# TUDSSL_condenar__Hardware_PCBs_Logger_Sc.net
KiCad netlist of a schematic drawn in Altium Designer
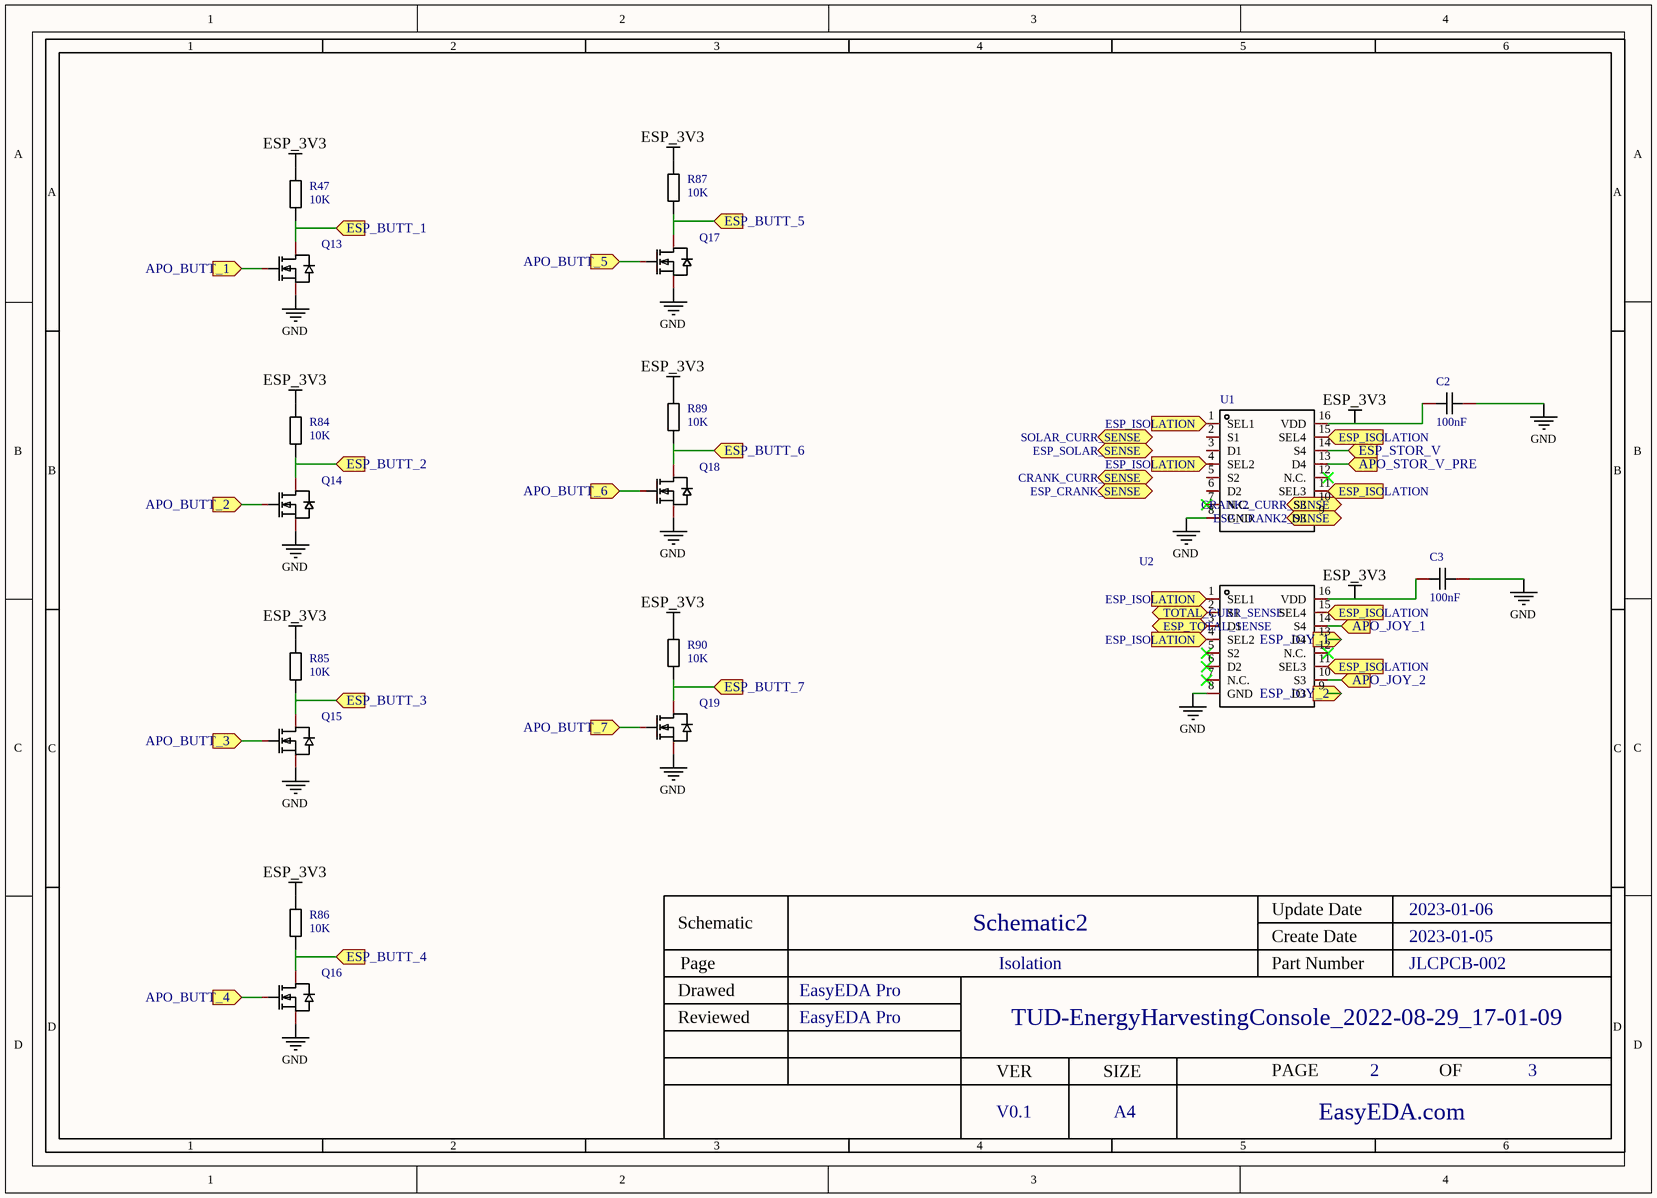
[diagram p0: TUDSSL_condenar__Hardware_PCBs_Logger_Schematic2__2_Isolation.schdoc]

(export (version "E")
  (design (tool "Eeschema 10.0.6"))
  (components
    (comp (ref "C2")
      (value "100nF")
      (fields
        (field (name "NAME") "100nF")
        (field (name "MANUFACTURER") "YAGEO")
        (field (name "MANUFACTURER PART") "CC0603KRX7R9BB104")
      )
      (libsource (lib "altium-import") (part "root_2_CC0603KRX7R9BB104_"))
    )
    (comp (ref "C3")
      (value "100nF")
      (fields
        (field (name "NAME") "100nF")
        (field (name "MANUFACTURER") "YAGEO")
        (field (name "MANUFACTURER PART") "CC0603KRX7R9BB104")
      )
      (libsource (lib "altium-import") (part "root_0_CC0603KRX7R9BB104_"))
    )
    (comp (ref "Q13")
      (value "SI2302")
      (fields (field (name "MANUFACTURER") "YONGYUTAI(永裕泰)"))
      (libsource (lib "altium-import") (part "root_0_SI2302_"))
    )
    (comp (ref "Q14")
      (value "SI2302")
      (fields (field (name "MANUFACTURER") "YONGYUTAI(永裕泰)"))
      (libsource (lib "altium-import") (part "root_0_SI2302_"))
    )
    (comp (ref "Q15")
      (value "SI2302")
      (fields (field (name "MANUFACTURER") "YONGYUTAI(永裕泰)"))
      (libsource (lib "altium-import") (part "root_0_SI2302_"))
    )
    (comp (ref "Q16")
      (value "SI2302")
      (fields (field (name "MANUFACTURER") "YONGYUTAI(永裕泰)"))
      (libsource (lib "altium-import") (part "root_0_SI2302_"))
    )
    (comp (ref "Q17")
      (value "SI2302")
      (fields (field (name "MANUFACTURER") "YONGYUTAI(永裕泰)"))
      (libsource (lib "altium-import") (part "root_0_SI2302_"))
    )
    (comp (ref "Q18")
      (value "SI2302")
      (fields (field (name "MANUFACTURER") "YONGYUTAI(永裕泰)"))
      (libsource (lib "altium-import") (part "root_0_SI2302_"))
    )
    (comp (ref "Q19")
      (value "SI2302")
      (fields (field (name "MANUFACTURER") "YONGYUTAI(永裕泰)"))
      (libsource (lib "altium-import") (part "root_0_SI2302_"))
    )
    (comp (ref "R47")
      (value "10K")
      (fields
        (field (name "NAME") "10K")
        (field (name "MANUFACTURER") "UniOhm")
        (field (name "MANUFACTURER PART") "0603WAF1002T5E")
      )
      (libsource (lib "altium-import") (part "root_3_0603WAF1002T5E_"))
    )
    (comp (ref "R84")
      (value "10K")
      (fields
        (field (name "NAME") "10K")
        (field (name "MANUFACTURER") "UniOhm")
        (field (name "MANUFACTURER PART") "0603WAF1002T5E")
      )
      (libsource (lib "altium-import") (part "root_3_0603WAF1002T5E_"))
    )
    (comp (ref "R85")
      (value "10K")
      (fields
        (field (name "NAME") "10K")
        (field (name "MANUFACTURER") "UniOhm")
        (field (name "MANUFACTURER PART") "0603WAF1002T5E")
      )
      (libsource (lib "altium-import") (part "root_3_0603WAF1002T5E_"))
    )
    (comp (ref "R86")
      (value "10K")
      (fields
        (field (name "NAME") "10K")
        (field (name "MANUFACTURER") "UniOhm")
        (field (name "MANUFACTURER PART") "0603WAF1002T5E")
      )
      (libsource (lib "altium-import") (part "root_3_0603WAF1002T5E_"))
    )
    (comp (ref "R87")
      (value "10K")
      (fields
        (field (name "NAME") "10K")
        (field (name "MANUFACTURER") "UniOhm")
        (field (name "MANUFACTURER PART") "0603WAF1002T5E")
      )
      (libsource (lib "altium-import") (part "root_3_0603WAF1002T5E_"))
    )
    (comp (ref "R89")
      (value "10K")
      (fields
        (field (name "NAME") "10K")
        (field (name "MANUFACTURER") "UniOhm")
        (field (name "MANUFACTURER PART") "0603WAF1002T5E")
      )
      (libsource (lib "altium-import") (part "root_3_0603WAF1002T5E_"))
    )
    (comp (ref "R90")
      (value "10K")
      (fields
        (field (name "NAME") "10K")
        (field (name "MANUFACTURER") "UniOhm")
        (field (name "MANUFACTURER PART") "0603WAF1002T5E")
      )
      (libsource (lib "altium-import") (part "root_3_0603WAF1002T5E_"))
    )
    (comp (ref "U1")
      (value "TMUX1511RSVR")
      (description "Switch Circuit:-")
      (fields (field (name "MANUFACTURER") "TI(德州仪器)"))
      (libsource (lib "altium-import") (part "root_0_TMUX1511RSVR_"))
    )
    (comp (ref "U2")
      (value "TMUX1511RSVR")
      (description "Switch Circuit:-")
      (fields (field (name "MANUFACTURER") "TI(德州仪器)"))
      (libsource (lib "altium-import") (part "root_0_TMUX1511RSVR_"))
    )
  )
  (nets
    (net (code "1") (name "/APO_BUTT_1") (class "Default")
      (node (ref "Q13") (pin "1") (pinfunction "G_1") (pintype "passive"))
    )
    (net (code "2") (name "/APO_BUTT_2") (class "Default")
      (node (ref "Q14") (pin "1") (pinfunction "G_1") (pintype "passive"))
    )
    (net (code "3") (name "/APO_BUTT_3") (class "Default")
      (node (ref "Q15") (pin "1") (pinfunction "G_1") (pintype "passive"))
    )
    (net (code "4") (name "/APO_BUTT_4") (class "Default")
      (node (ref "Q16") (pin "1") (pinfunction "G_1") (pintype "passive"))
    )
    (net (code "5") (name "/APO_BUTT_5") (class "Default")
      (node (ref "Q17") (pin "1") (pinfunction "G_1") (pintype "passive"))
    )
    (net (code "6") (name "/APO_BUTT_6") (class "Default")
      (node (ref "Q18") (pin "1") (pinfunction "G_1") (pintype "passive"))
    )
    (net (code "7") (name "/APO_BUTT_7") (class "Default")
      (node (ref "Q19") (pin "1") (pinfunction "G_1") (pintype "passive"))
    )
    (net (code "8") (name "/APO_JOY_1") (class "Default")
      (node (ref "U2") (pin "14") (pinfunction "S4_14") (pintype "passive"))
    )
    (net (code "9") (name "/APO_JOY_2") (class "Default")
      (node (ref "U2") (pin "10") (pinfunction "S3_10") (pintype "passive"))
    )
    (net (code "10") (name "/APO_STOR_V_PRE") (class "Default")
      (node (ref "U1") (pin "13") (pinfunction "D4_13") (pintype "passive"))
    )
    (net (code "13") (name "/ESP_BUTT_1") (class "Default")
      (node (ref "Q13") (pin "3") (pinfunction "D_3") (pintype "passive"))
      (node (ref "R47") (pin "2") (pinfunction "2_2") (pintype "passive"))
    )
    (net (code "14") (name "/ESP_BUTT_2") (class "Default")
      (node (ref "Q14") (pin "3") (pinfunction "D_3") (pintype "passive"))
      (node (ref "R84") (pin "2") (pinfunction "2_2") (pintype "passive"))
    )
    (net (code "15") (name "/ESP_BUTT_3") (class "Default")
      (node (ref "Q15") (pin "3") (pinfunction "D_3") (pintype "passive"))
      (node (ref "R85") (pin "2") (pinfunction "2_2") (pintype "passive"))
    )
    (net (code "16") (name "/ESP_BUTT_4") (class "Default")
      (node (ref "Q16") (pin "3") (pinfunction "D_3") (pintype "passive"))
      (node (ref "R86") (pin "2") (pinfunction "2_2") (pintype "passive"))
    )
    (net (code "17") (name "/ESP_BUTT_5") (class "Default")
      (node (ref "Q17") (pin "3") (pinfunction "D_3") (pintype "passive"))
      (node (ref "R87") (pin "2") (pinfunction "2_2") (pintype "passive"))
    )
    (net (code "18") (name "/ESP_BUTT_6") (class "Default")
      (node (ref "Q18") (pin "3") (pinfunction "D_3") (pintype "passive"))
      (node (ref "R89") (pin "2") (pinfunction "2_2") (pintype "passive"))
    )
    (net (code "19") (name "/ESP_BUTT_7") (class "Default")
      (node (ref "Q19") (pin "3") (pinfunction "D_3") (pintype "passive"))
      (node (ref "R90") (pin "2") (pinfunction "2_2") (pintype "passive"))
    )
    (net (code "22") (name "/ESP_ISOLATION") (class "Default")
      (node (ref "U1") (pin "1") (pinfunction "SEL1_1") (pintype "passive"))
      (node (ref "U1") (pin "11") (pinfunction "SEL3_11") (pintype "passive"))
      (node (ref "U1") (pin "15") (pinfunction "SEL4_15") (pintype "passive"))
      (node (ref "U1") (pin "4") (pinfunction "SEL2_4") (pintype "passive"))
      (node (ref "U2") (pin "1") (pinfunction "SEL1_1") (pintype "passive"))
      (node (ref "U2") (pin "11") (pinfunction "SEL3_11") (pintype "passive"))
      (node (ref "U2") (pin "15") (pinfunction "SEL4_15") (pintype "passive"))
      (node (ref "U2") (pin "4") (pinfunction "SEL2_4") (pintype "passive"))
    )
    (net (code "23") (name "/ESP_JOY_1") (class "Default")
      (node (ref "U2") (pin "13") (pinfunction "D4_13") (pintype "passive"))
    )
    (net (code "24") (name "/ESP_JOY_2") (class "Default")
      (node (ref "U2") (pin "9") (pinfunction "D3_9") (pintype "passive"))
    )
    (net (code "26") (name "/ESP_STOR_V") (class "Default")
      (node (ref "U1") (pin "14") (pinfunction "S4_14") (pintype "passive"))
    )
    (net (code "30") (name "ESP_3V3") (class "Default")
      (node (ref "C2") (pin "2") (pinfunction "2_2") (pintype "passive"))
      (node (ref "C3") (pin "1") (pinfunction "1_1") (pintype "passive"))
      (node (ref "R47") (pin "1") (pinfunction "1_1") (pintype "passive"))
      (node (ref "R84") (pin "1") (pinfunction "1_1") (pintype "passive"))
      (node (ref "R85") (pin "1") (pinfunction "1_1") (pintype "passive"))
      (node (ref "R86") (pin "1") (pinfunction "1_1") (pintype "passive"))
      (node (ref "R87") (pin "1") (pinfunction "1_1") (pintype "passive"))
      (node (ref "R89") (pin "1") (pinfunction "1_1") (pintype "passive"))
      (node (ref "R90") (pin "1") (pinfunction "1_1") (pintype "passive"))
      (node (ref "U1") (pin "16") (pinfunction "VDD_16") (pintype "passive"))
      (node (ref "U2") (pin "16") (pinfunction "VDD_16") (pintype "passive"))
    )
    (net (code "31") (name "GND") (class "Default")
      (node (ref "C2") (pin "1") (pinfunction "1_1") (pintype "passive"))
      (node (ref "C3") (pin "2") (pinfunction "2_2") (pintype "passive"))
      (node (ref "Q13") (pin "2") (pinfunction "S_2") (pintype "passive"))
      (node (ref "Q14") (pin "2") (pinfunction "S_2") (pintype "passive"))
      (node (ref "Q15") (pin "2") (pinfunction "S_2") (pintype "passive"))
      (node (ref "Q16") (pin "2") (pinfunction "S_2") (pintype "passive"))
      (node (ref "Q17") (pin "2") (pinfunction "S_2") (pintype "passive"))
      (node (ref "Q18") (pin "2") (pinfunction "S_2") (pintype "passive"))
      (node (ref "Q19") (pin "2") (pinfunction "S_2") (pintype "passive"))
      (node (ref "U1") (pin "8") (pinfunction "GND_8") (pintype "passive"))
      (node (ref "U2") (pin "8") (pinfunction "GND_8") (pintype "passive"))
    )
    (net (code "32") (name "unconnected-(U1-D1-Pad3)") (class "Default")
      (node (ref "U1") (pin "3") (pinfunction "D1_3") (pintype "passive"))
    )
    (net (code "33") (name "unconnected-(U1-D2-Pad6)") (class "Default")
      (node (ref "U1") (pin "6") (pinfunction "D2_6") (pintype "passive"))
    )
    (net (code "34") (name "unconnected-(U1-D3-Pad9)") (class "Default")
      (node (ref "U1") (pin "9") (pinfunction "D3_9") (pintype "passive"))
    )
    (net (code "35") (name "unconnected-(U1-N.C.-Pad7)") (class "Default")
      (node (ref "U1") (pin "7") (pinfunction "N.C._7") (pintype "passive+no_connect"))
    )
    (net (code "36") (name "unconnected-(U1-N.C.-Pad12)") (class "Default")
      (node (ref "U1") (pin "12") (pinfunction "N.C._12") (pintype "passive+no_connect"))
    )
    (net (code "37") (name "unconnected-(U1-S1-Pad2)") (class "Default")
      (node (ref "U1") (pin "2") (pinfunction "S1_2") (pintype "passive"))
    )
    (net (code "38") (name "unconnected-(U1-S2-Pad5)") (class "Default")
      (node (ref "U1") (pin "5") (pinfunction "S2_5") (pintype "passive"))
    )
    (net (code "39") (name "unconnected-(U1-S3-Pad10)") (class "Default")
      (node (ref "U1") (pin "10") (pinfunction "S3_10") (pintype "passive"))
    )
    (net (code "40") (name "unconnected-(U2-D1-Pad3)") (class "Default")
      (node (ref "U2") (pin "3") (pinfunction "D1_3") (pintype "passive"))
    )
    (net (code "41") (name "unconnected-(U2-D2-Pad6)") (class "Default")
      (node (ref "U2") (pin "6") (pinfunction "D2_6") (pintype "passive+no_connect"))
    )
    (net (code "42") (name "unconnected-(U2-N.C.-Pad7)") (class "Default")
      (node (ref "U2") (pin "7") (pinfunction "N.C._7") (pintype "passive+no_connect"))
    )
    (net (code "43") (name "unconnected-(U2-N.C.-Pad12)") (class "Default")
      (node (ref "U2") (pin "12") (pinfunction "N.C._12") (pintype "passive+no_connect"))
    )
    (net (code "44") (name "unconnected-(U2-S1-Pad2)") (class "Default")
      (node (ref "U2") (pin "2") (pinfunction "S1_2") (pintype "passive"))
    )
    (net (code "45") (name "unconnected-(U2-S2-Pad5)") (class "Default")
      (node (ref "U2") (pin "5") (pinfunction "S2_5") (pintype "passive+no_connect"))
    )
  )
)
